# Magnetventil_Ansteuerung.net
KiCad netlist of a schematic drawn in EAGLE
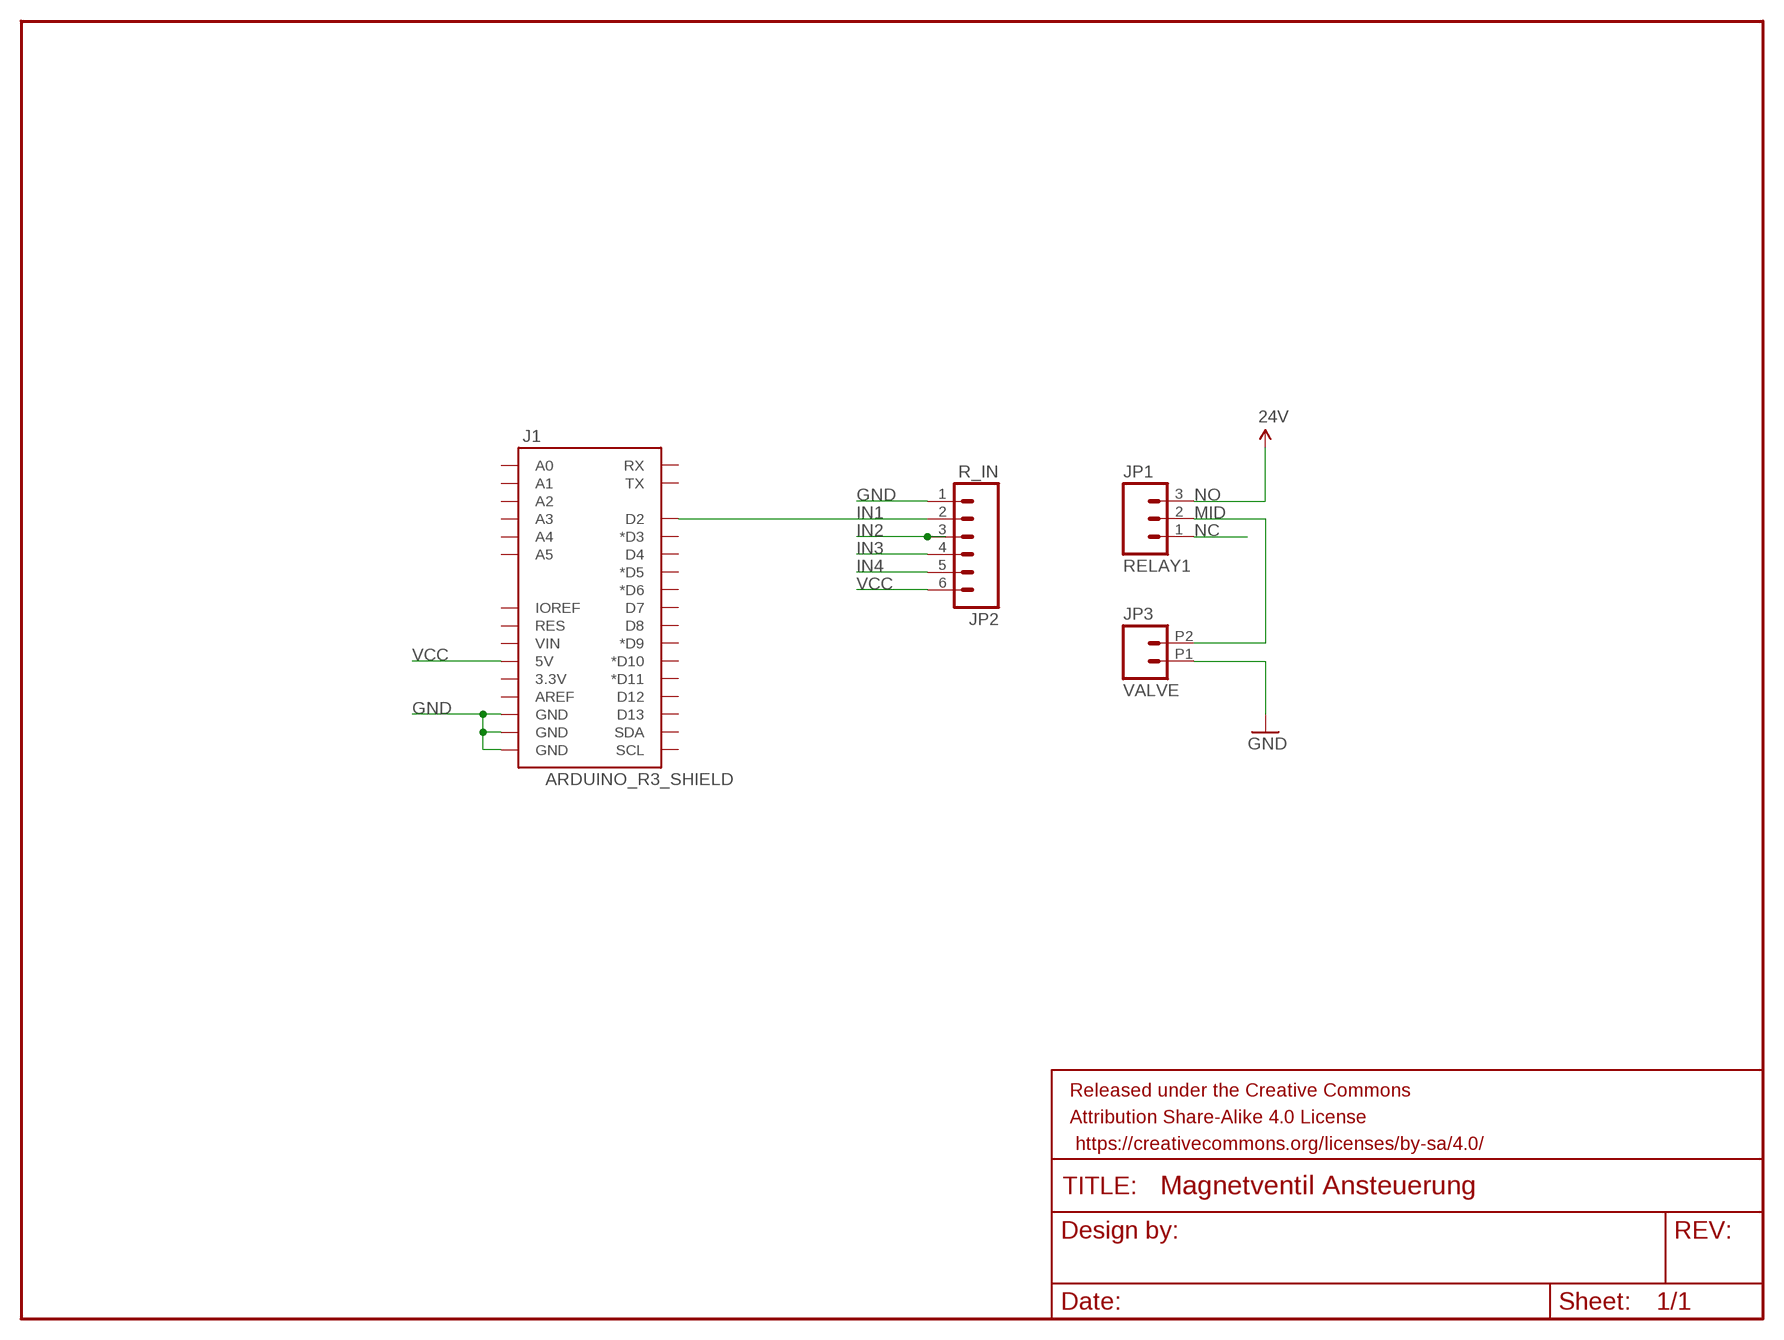
[diagram p0: schematic, sheet 1]

(export (version "E")
  (design (tool "Eeschema 10.0.6"))
  (components
    (comp (ref "FRAME1")
      (value "FRAME-LETTER")
      (footprint "eagle-import:CREATIVE_COMMONS")
      (fields (field (name "DESIGNER") "NAME"))
      (libsource (lib "eagle-import") (part "FRAME-LETTER"))
    )
    (comp (ref "J1")
      (value "ARDUINO_R3_SHIELD")
      (footprint "eagle-import:UNO_R3_SHIELD")
      (libsource (lib "eagle-import") (part "ARDUINO_R3_SHIELD"))
    )
    (comp (ref "JP1")
      (value "RELAY1")
      (footprint "eagle-import:SCREWTERMINAL-5MM-3")
      (libsource (lib "eagle-import") (part "M03-SCREW-5MM"))
    )
    (comp (ref "JP2")
      (value "R_IN")
      (footprint "eagle-import:1X06_LOCK")
      (libsource (lib "eagle-import") (part "M06LOCK"))
    )
    (comp (ref "JP3")
      (value "VALVE")
      (footprint "eagle-import:1X02_2.54_SCREWTERM")
      (libsource (lib "eagle-import") (part "M022.54MM_SCREWTERM"))
    )
  )
  (nets
    (net (code "1") (name "/IN1") (class "Default")
      (node (ref "J1") (pin "D2") (pinfunction "D2_D2") (pintype "bidirectional"))
      (node (ref "JP2") (pin "2") (pinfunction "2_2") (pintype "passive"))
    )
    (net (code "2") (name "/IN2") (class "Default")
      (node (ref "JP2") (pin "3") (pinfunction "3_3") (pintype "passive"))
    )
    (net (code "3") (name "/IN3") (class "Default")
      (node (ref "JP2") (pin "4") (pinfunction "4_4") (pintype "passive"))
    )
    (net (code "4") (name "/IN4") (class "Default")
      (node (ref "JP2") (pin "5") (pinfunction "5_5") (pintype "passive"))
    )
    (net (code "5") (name "/MID") (class "Default")
      (node (ref "JP1") (pin "2") (pinfunction "2_2") (pintype "passive"))
      (node (ref "JP3") (pin "P2") (pinfunction "2_P2") (pintype "passive"))
    )
    (net (code "6") (name "/NC") (class "Default")
      (node (ref "JP1") (pin "1") (pinfunction "1_1") (pintype "passive"))
    )
    (net (code "7") (name "/VCC") (class "Default")
      (node (ref "J1") (pin "5V") (pinfunction "5V_5V") (pintype "bidirectional"))
      (node (ref "JP2") (pin "6") (pinfunction "6_6") (pintype "passive"))
    )
    (net (code "8") (name "24V") (class "Default")
      (node (ref "JP1") (pin "3") (pinfunction "3_3") (pintype "passive"))
    )
    (net (code "9") (name "GND") (class "Default")
      (node (ref "J1") (pin "GND@0") (pinfunction "GND_GND@0") (pintype "bidirectional"))
      (node (ref "J1") (pin "GND@1") (pinfunction "GND_GND@1") (pintype "bidirectional"))
      (node (ref "J1") (pin "GND@2") (pinfunction "GND_GND@2") (pintype "bidirectional"))
      (node (ref "JP2") (pin "1") (pinfunction "1_1") (pintype "passive"))
      (node (ref "JP3") (pin "P1") (pinfunction "1_P1") (pintype "passive"))
    )
    (net (code "10") (name "unconnected-(J1-*D3-PadD3)") (class "Default")
      (node (ref "J1") (pin "D3") (pinfunction "*D3_D3") (pintype "bidirectional"))
    )
    (net (code "11") (name "unconnected-(J1-*D5-PadD5)") (class "Default")
      (node (ref "J1") (pin "D5") (pinfunction "*D5_D5") (pintype "bidirectional"))
    )
    (net (code "12") (name "unconnected-(J1-*D6-PadD6)") (class "Default")
      (node (ref "J1") (pin "D6") (pinfunction "*D6_D6") (pintype "bidirectional"))
    )
    (net (code "13") (name "unconnected-(J1-*D9-PadD9)") (class "Default")
      (node (ref "J1") (pin "D9") (pinfunction "*D9_D9") (pintype "bidirectional"))
    )
    (net (code "14") (name "unconnected-(J1-*D10-PadD10)") (class "Default")
      (node (ref "J1") (pin "D10") (pinfunction "*D10_D10") (pintype "bidirectional"))
    )
    (net (code "15") (name "unconnected-(J1-*D11-PadD11)") (class "Default")
      (node (ref "J1") (pin "D11") (pinfunction "*D11_D11") (pintype "bidirectional"))
    )
    (net (code "16") (name "unconnected-(J1-Pad3.3V)") (class "Default")
      (node (ref "J1") (pin "3.3V") (pinfunction "3.3V_3.3V") (pintype "bidirectional"))
    )
    (net (code "17") (name "unconnected-(J1-PadA0)") (class "Default")
      (node (ref "J1") (pin "A0") (pinfunction "A0_A0") (pintype "bidirectional"))
    )
    (net (code "18") (name "unconnected-(J1-PadA1)") (class "Default")
      (node (ref "J1") (pin "A1") (pinfunction "A1_A1") (pintype "bidirectional"))
    )
    (net (code "19") (name "unconnected-(J1-PadA2)") (class "Default")
      (node (ref "J1") (pin "A2") (pinfunction "A2_A2") (pintype "bidirectional"))
    )
    (net (code "20") (name "unconnected-(J1-PadA3)") (class "Default")
      (node (ref "J1") (pin "A3") (pinfunction "A3_A3") (pintype "bidirectional"))
    )
    (net (code "21") (name "unconnected-(J1-PadA4)") (class "Default")
      (node (ref "J1") (pin "A4") (pinfunction "A4_A4") (pintype "bidirectional"))
    )
    (net (code "22") (name "unconnected-(J1-PadA5)") (class "Default")
      (node (ref "J1") (pin "A5") (pinfunction "A5_A5") (pintype "bidirectional"))
    )
    (net (code "23") (name "unconnected-(J1-PadAREF)") (class "Default")
      (node (ref "J1") (pin "AREF") (pinfunction "AREF_AREF") (pintype "bidirectional"))
    )
    (net (code "24") (name "unconnected-(J1-PadD4)") (class "Default")
      (node (ref "J1") (pin "D4") (pinfunction "D4_D4") (pintype "bidirectional"))
    )
    (net (code "25") (name "unconnected-(J1-PadD7)") (class "Default")
      (node (ref "J1") (pin "D7") (pinfunction "D7_D7") (pintype "bidirectional"))
    )
    (net (code "26") (name "unconnected-(J1-PadD8)") (class "Default")
      (node (ref "J1") (pin "D8") (pinfunction "D8_D8") (pintype "bidirectional"))
    )
    (net (code "27") (name "unconnected-(J1-PadD12)") (class "Default")
      (node (ref "J1") (pin "D12") (pinfunction "D12_D12") (pintype "bidirectional"))
    )
    (net (code "28") (name "unconnected-(J1-PadD13)") (class "Default")
      (node (ref "J1") (pin "D13") (pinfunction "D13_D13") (pintype "bidirectional"))
    )
    (net (code "29") (name "unconnected-(J1-PadIOREF)") (class "Default")
      (node (ref "J1") (pin "IOREF") (pinfunction "IOREF_IOREF") (pintype "bidirectional"))
    )
    (net (code "30") (name "unconnected-(J1-PadRES)") (class "Default")
      (node (ref "J1") (pin "RES") (pinfunction "RES_RES") (pintype "bidirectional"))
    )
    (net (code "31") (name "unconnected-(J1-PadRX)") (class "Default")
      (node (ref "J1") (pin "RX") (pinfunction "RX_RX") (pintype "bidirectional"))
    )
    (net (code "32") (name "unconnected-(J1-PadSCL)") (class "Default")
      (node (ref "J1") (pin "SCL") (pinfunction "SCL_SCL") (pintype "bidirectional"))
    )
    (net (code "33") (name "unconnected-(J1-PadSDA)") (class "Default")
      (node (ref "J1") (pin "SDA") (pinfunction "SDA_SDA") (pintype "bidirectional"))
    )
    (net (code "34") (name "unconnected-(J1-PadTX)") (class "Default")
      (node (ref "J1") (pin "TX") (pinfunction "TX_TX") (pintype "bidirectional"))
    )
    (net (code "35") (name "unconnected-(J1-PadVIN)") (class "Default")
      (node (ref "J1") (pin "VIN") (pinfunction "VIN_VIN") (pintype "bidirectional"))
    )
  )
)
